# SW6106_A_A_B_C_MCU_LED.net
KiCad netlist of a schematic drawn in Altium Designer
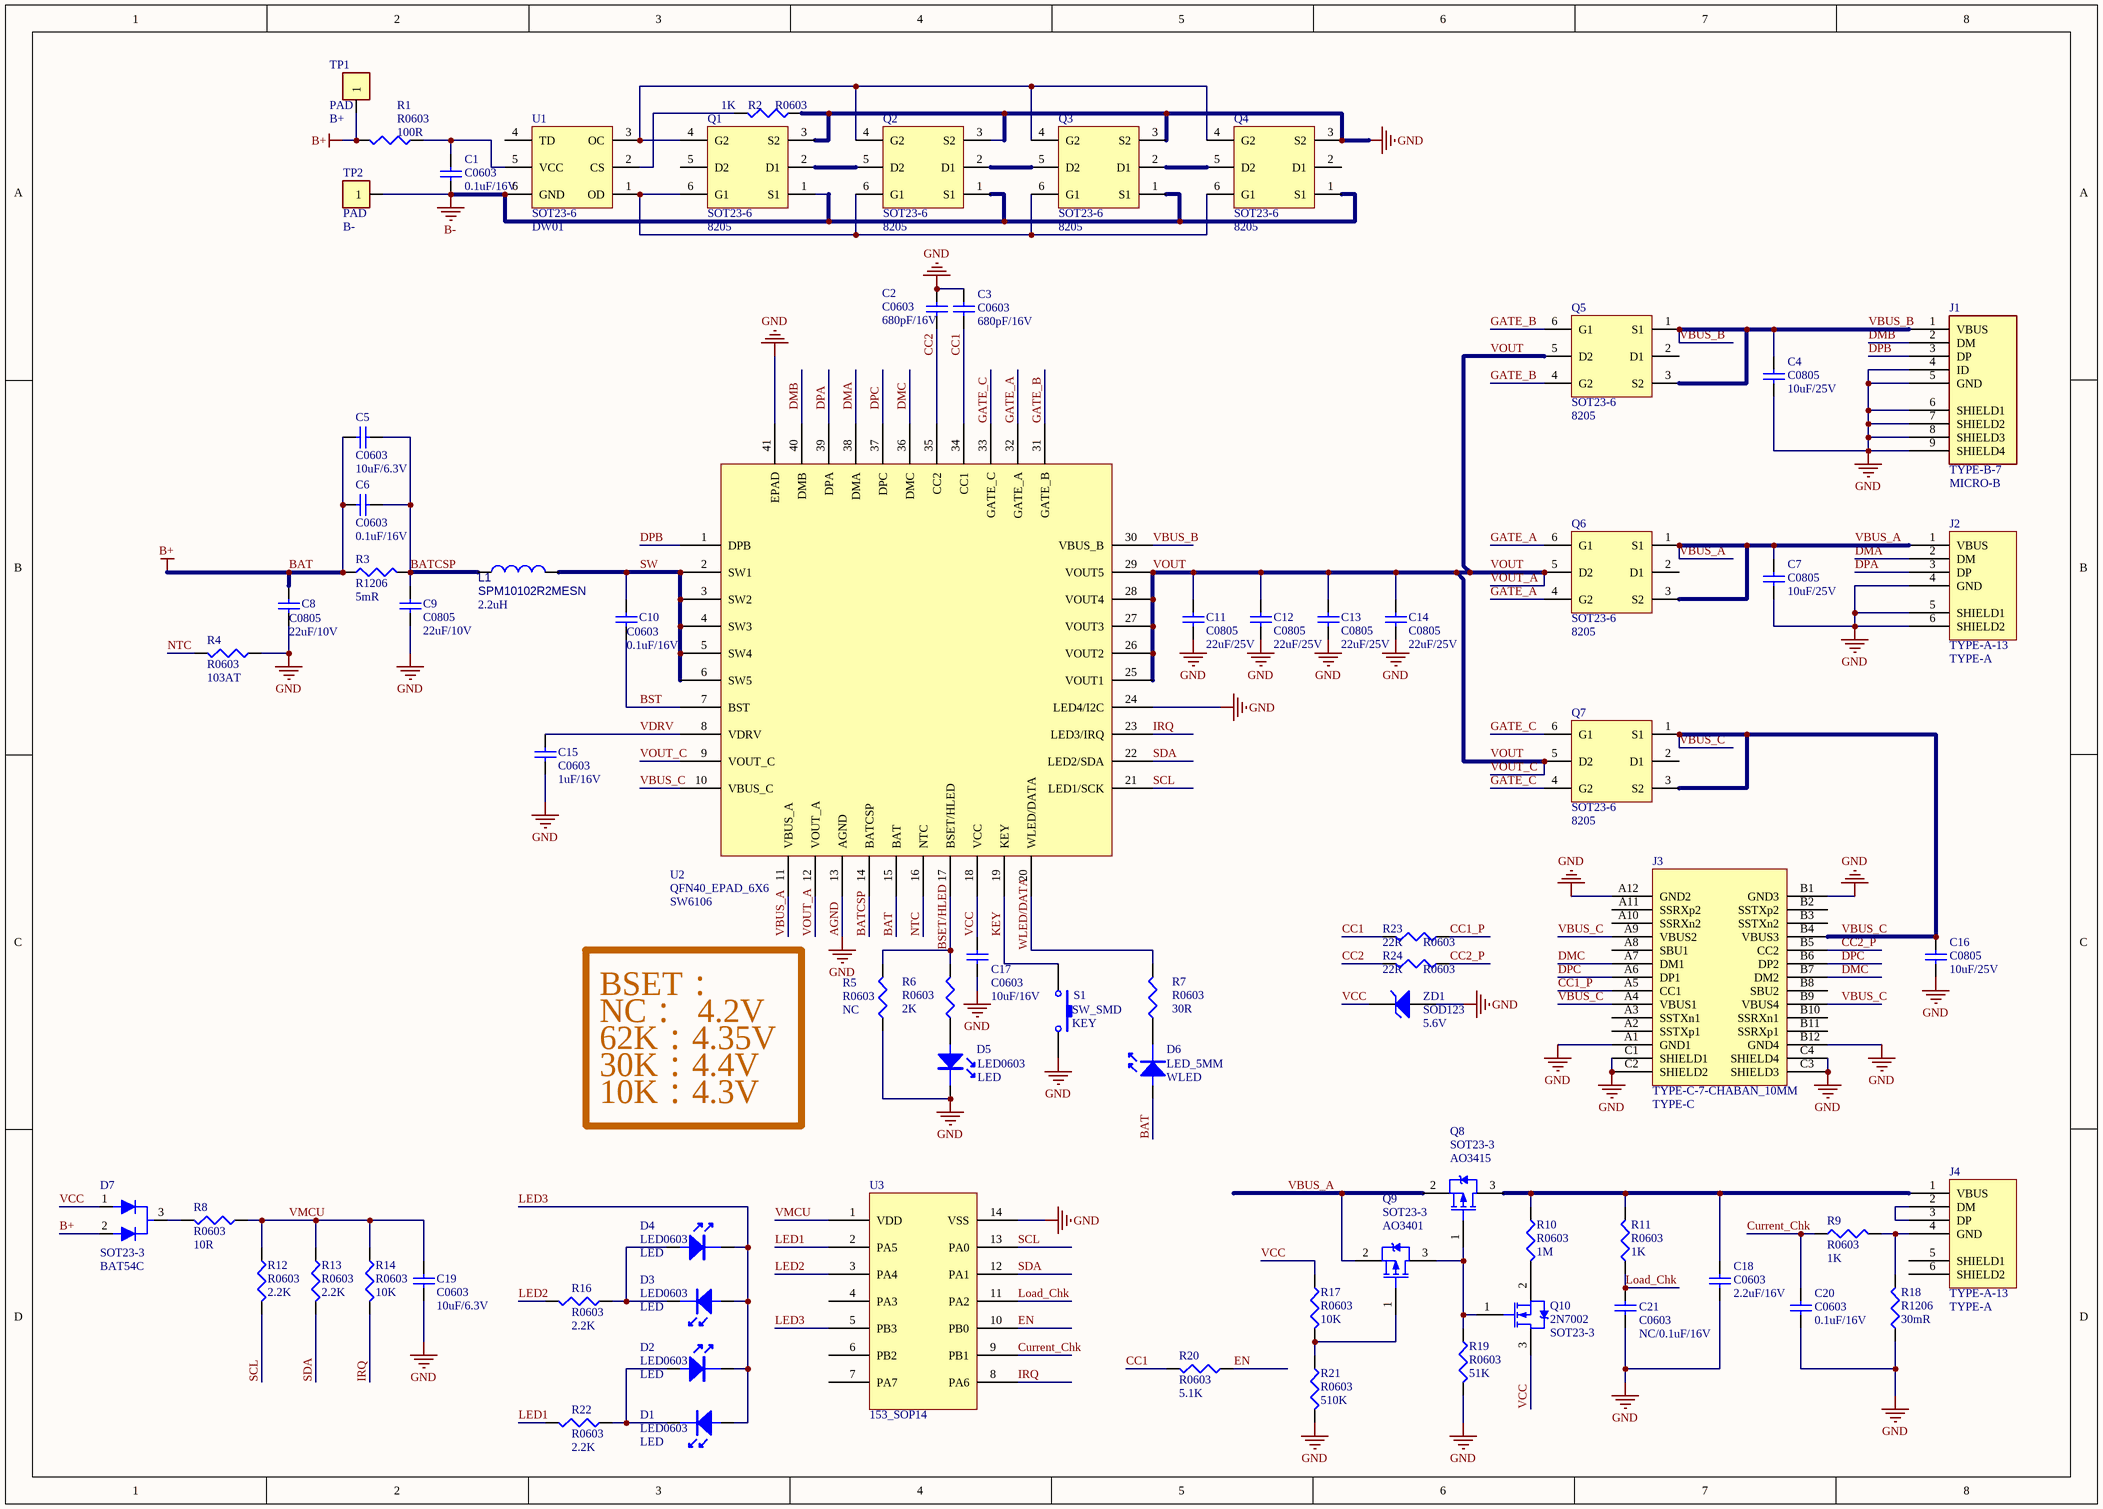
[diagram p0: SW6106+A+A+B+C+MCU+LED.SchDoc]

(export (version "E")
  (design (tool "Eeschema 10.0.6"))
  (components
    (comp (ref "C1")
      (value "C0603")
      (footprint "C0603")
      (description "Capacitor")
      (fields (field (name "ALTIUM_VALUE") "0.1uF/16V") (field (name "PUBLISHER") "Altium Limited"))
      (libsource (lib "*") (part "Cap"))
    )
    (comp (ref "C2")
      (value "C0603")
      (footprint "C0603")
      (description "Capacitor")
      (fields (field (name "ALTIUM_VALUE") "680pF/16V") (field (name "PUBLISHER") "Altium Limited"))
      (libsource (lib "*") (part "CAP0603"))
    )
    (comp (ref "C3")
      (value "C0603")
      (footprint "C0603")
      (description "Capacitor")
      (fields (field (name "ALTIUM_VALUE") "680pF/16V") (field (name "PUBLISHER") "Altium Limited"))
      (libsource (lib "*") (part "CAP0603"))
    )
    (comp (ref "C4")
      (value "C0805")
      (footprint "C0805")
      (description "Capacitor")
      (fields (field (name "ALTIUM_VALUE") "10uF/25V") (field (name "PUBLISHER") "Altium Limited"))
      (libsource (lib "*") (part "CAP0603"))
    )
    (comp (ref "C5")
      (value "C0603")
      (footprint "C0603")
      (description "Capacitor")
      (fields (field (name "ALTIUM_VALUE") "10uF/6.3V") (field (name "PUBLISHER") "Altium Limited"))
      (libsource (lib "*") (part "CAP0603"))
    )
    (comp (ref "C6")
      (value "C0603")
      (footprint "C0603")
      (description "Capacitor")
      (fields (field (name "ALTIUM_VALUE") "0.1uF/16V") (field (name "PUBLISHER") "Altium Limited"))
      (libsource (lib "*") (part "CAP0603"))
    )
    (comp (ref "C7")
      (value "C0805")
      (footprint "C0805")
      (description "Capacitor")
      (fields (field (name "ALTIUM_VALUE") "10uF/25V") (field (name "PUBLISHER") "Altium Limited"))
      (libsource (lib "*") (part "CAP0603"))
    )
    (comp (ref "C8")
      (value "C0805")
      (footprint "C0805")
      (description "Capacitor")
      (fields (field (name "ALTIUM_VALUE") "22uF/10V") (field (name "PUBLISHER") "Altium Limited"))
      (libsource (lib "*") (part "CAP0805"))
    )
    (comp (ref "C9")
      (value "C0805")
      (footprint "C0805")
      (description "Capacitor")
      (fields (field (name "ALTIUM_VALUE") "22uF/10V") (field (name "PUBLISHER") "Altium Limited"))
      (libsource (lib "*") (part "CAP0805"))
    )
    (comp (ref "C10")
      (value "C0603")
      (footprint "C0603")
      (description "Capacitor")
      (fields (field (name "ALTIUM_VALUE") "0.1uF/16V") (field (name "PUBLISHER") "Altium Limited"))
      (libsource (lib "*") (part "CAP0603"))
    )
    (comp (ref "C11")
      (value "C0805")
      (footprint "C0805")
      (description "Capacitor")
      (fields (field (name "ALTIUM_VALUE") "22uF/25V") (field (name "PUBLISHER") "Altium Limited"))
      (libsource (lib "*") (part "CAP0805"))
    )
    (comp (ref "C12")
      (value "C0805")
      (footprint "C0805")
      (description "Capacitor")
      (fields (field (name "ALTIUM_VALUE") "22uF/25V") (field (name "PUBLISHER") "Altium Limited"))
      (libsource (lib "*") (part "CAP0805"))
    )
    (comp (ref "C13")
      (value "C0805")
      (footprint "C0805")
      (description "Capacitor")
      (fields (field (name "ALTIUM_VALUE") "22uF/25V") (field (name "PUBLISHER") "Altium Limited"))
      (libsource (lib "*") (part "CAP0805"))
    )
    (comp (ref "C14")
      (value "C0805")
      (footprint "C0805")
      (description "Capacitor")
      (fields (field (name "ALTIUM_VALUE") "22uF/25V") (field (name "PUBLISHER") "Altium Limited"))
      (libsource (lib "*") (part "CAP0805"))
    )
    (comp (ref "C15")
      (value "C0603")
      (footprint "C0603")
      (description "Capacitor")
      (fields (field (name "ALTIUM_VALUE") "1uF/16V") (field (name "PUBLISHER") "Altium Limited"))
      (libsource (lib "*") (part "CAP0603"))
    )
    (comp (ref "C16")
      (value "C0805")
      (footprint "C0805")
      (description "Capacitor")
      (fields (field (name "ALTIUM_VALUE") "10uF/25V") (field (name "PUBLISHER") "Altium Limited"))
      (libsource (lib "*") (part "CAP0603"))
    )
    (comp (ref "C17")
      (value "C0603")
      (footprint "C0603")
      (description "Capacitor")
      (fields (field (name "ALTIUM_VALUE") "10uF/16V") (field (name "PUBLISHER") "Altium Limited"))
      (libsource (lib "*") (part "CAP0603"))
    )
    (comp (ref "C18")
      (value "C0603")
      (footprint "C0603")
      (description "Capacitor")
      (fields (field (name "ALTIUM_VALUE") "2.2uF/16V") (field (name "PUBLISHER") "Altium Limited"))
      (libsource (lib "*") (part "CAP0603"))
    )
    (comp (ref "C19")
      (value "C0603")
      (footprint "C0603")
      (description "Capacitor")
      (fields (field (name "ALTIUM_VALUE") "10uF/6.3V") (field (name "PUBLISHER") "Altium Limited"))
      (libsource (lib "*") (part "CAP0603"))
    )
    (comp (ref "C20")
      (value "C0603")
      (footprint "C0603")
      (description "Capacitor")
      (fields (field (name "ALTIUM_VALUE") "0.1uF/16V") (field (name "PUBLISHER") "Altium Limited"))
      (libsource (lib "*") (part "CAP0603"))
    )
    (comp (ref "C21")
      (value "C0603")
      (footprint "C0603")
      (description "Capacitor")
      (fields (field (name "ALTIUM_VALUE") "NC/0.1uF/16V") (field (name "PUBLISHER") "Altium Limited"))
      (libsource (lib "*") (part "CAP0603"))
    )
    (comp (ref "D1") (value "LED") (footprint "LED0603") (libsource (lib "*") (part "LED")))
    (comp (ref "D2") (value "LED") (footprint "LED0603") (libsource (lib "*") (part "LED")))
    (comp (ref "D3") (value "LED") (footprint "LED0603") (libsource (lib "*") (part "LED")))
    (comp (ref "D4") (value "LED") (footprint "LED0603") (libsource (lib "*") (part "LED")))
    (comp (ref "D5") (value "LED") (footprint "LED0603") (libsource (lib "*") (part "LED")))
    (comp (ref "D6")
      (value "WLED")
      (footprint "LED_5MM")
      (fields (field (name "FOOTPRINF") "LED_5MM") (field (name "Comment") "LED_5MM"))
      (libsource (lib "*") (part "LED"))
    )
    (comp (ref "D7") (value "BAT54C") (footprint "SOT23-3") (libsource (lib "Schlib1-2012") (part "D3")))
    (comp (ref "J1")
      (value "MICRO-B")
      (footprint "TYPE-B-7")
      (fields (field (name "FOOTPRINTF") "TYPE-B-7") (field (name "Comment") "USB_MICRO_B"))
      (libsource (lib "*") (part "USB_MICRO_B"))
    )
    (comp (ref "J2")
      (value "TYPE-A")
      (footprint "TYPE-A-13")
      (fields (field (name "FOOTPRINF") "TYPE-A-13") (field (name "Comment") "TYPE-A-1"))
      (libsource (lib "*") (part "TYPE-A-1"))
    )
    (comp (ref "J3")
      (value "TYPE-C")
      (footprint "TYPE-C-7-CHABAN_10MM")
      (libsource (lib "*") (part "TYPE-C"))
    )
    (comp (ref "J4")
      (value "TYPE-A")
      (footprint "PIE10-USB")
      (fields (field (name "FOOTPRINF") "TYPE-A-13") (field (name "Comment") "TYPE-A-1"))
      (libsource (lib "*") (part "TYPE-A-1"))
    )
    (comp (ref "L1")
      (value "SPM10102R2MESN")
      (footprint "INDUCTOR_SPM1010")
      (fields (field (name "ALTIUM_VALUE") "2.2uH"))
      (libsource (lib "*") (part "INDUCTOR"))
    )
    (comp (ref "Q1")
      (value "8205")
      (footprint "SOT23-6")
      (fields (field (name "FOOTPRINF") "SOT23-6"))
      (libsource (lib "*") (part "8205B"))
    )
    (comp (ref "Q2")
      (value "8205")
      (footprint "SOT23-6")
      (fields (field (name "FOOTPRINF") "SOT23-6"))
      (libsource (lib "*") (part "8205B"))
    )
    (comp (ref "Q3")
      (value "8205")
      (footprint "SOT23-6")
      (fields (field (name "FOOTPRINF") "SOT23-6"))
      (libsource (lib "*") (part "8205B"))
    )
    (comp (ref "Q4")
      (value "8205")
      (footprint "SOT23-6")
      (fields (field (name "FOOTPRINF") "SOT23-6"))
      (libsource (lib "*") (part "8205B"))
    )
    (comp (ref "Q5")
      (value "8205")
      (footprint "SOT23-6")
      (fields (field (name "FOOTPRINF") "SOT23-6"))
      (libsource (lib "") (part "8205B_1"))
    )
    (comp (ref "Q6")
      (value "8205")
      (footprint "SOT23-6")
      (fields (field (name "FOOTPRINF") "SOT23-6"))
      (libsource (lib "") (part "8205B_1"))
    )
    (comp (ref "Q7")
      (value "8205")
      (footprint "SOT23-6")
      (fields (field (name "FOOTPRINF") "SOT23-6"))
      (libsource (lib "") (part "8205B_1"))
    )
    (comp (ref "Q8")
      (value "AO3415")
      (footprint "SOT23-3")
      (description "P-Channel Power MOSFET")
      (fields (field (name "Comment") "PMOS-2") (field (name "PUBLISHER") "Altium Limited"))
      (libsource (lib "Miscellaneous Devices") (part "PMOS-2"))
    )
    (comp (ref "Q9")
      (value "AO3401")
      (footprint "SOT23-3")
      (description "P-Channel Power MOSFET")
      (fields (field (name "Comment") "PMOS-2") (field (name "PUBLISHER") "Altium Limited"))
      (libsource (lib "Miscellaneous Devices") (part "PMOS-2"))
    )
    (comp (ref "Q10")
      (value "2N7002")
      (footprint "SOT23-3")
      (description "N-Channel Power MOSFET")
      (fields (field (name "Comment") "NMOS-2") (field (name "PUBLISHER") "Altium Limited"))
      (libsource (lib "Miscellaneous Devices") (part "NMOS-2"))
    )
    (comp (ref "R1")
      (value "R0603")
      (footprint "R0603")
      (description "Resistor")
      (fields (field (name "ALTIUM_VALUE") "100R") (field (name "PUBLISHER") "Altium Limited"))
      (libsource (lib "*") (part "Res3"))
    )
    (comp (ref "R2")
      (value "R0603")
      (footprint "R0603")
      (description "Resistor")
      (fields (field (name "ALTIUM_VALUE") "1K") (field (name "PUBLISHER") "Altium Limited"))
      (libsource (lib "*") (part "Res3"))
    )
    (comp (ref "R3")
      (value "R1206")
      (footprint "R1206")
      (description "Resistor")
      (fields (field (name "ALTIUM_VALUE") "5mR") (field (name "PUBLISHER") "Altium Limited"))
      (libsource (lib "*") (part "RES"))
    )
    (comp (ref "R4")
      (value "R0603")
      (footprint "R0603")
      (description "Resistor")
      (fields (field (name "ALTIUM_VALUE") "103AT") (field (name "PUBLISHER") "Altium Limited"))
      (libsource (lib "*") (part "RES"))
    )
    (comp (ref "R5")
      (value "R0603")
      (footprint "R0603")
      (description "Resistor")
      (fields (field (name "ALTIUM_VALUE") "NC") (field (name "PUBLISHER") "Altium Limited"))
      (libsource (lib "*") (part "RES"))
    )
    (comp (ref "R6")
      (value "R0603")
      (footprint "R0603")
      (description "Resistor")
      (fields (field (name "ALTIUM_VALUE") "2K") (field (name "PUBLISHER") "Altium Limited"))
      (libsource (lib "*") (part "RES"))
    )
    (comp (ref "R7")
      (value "R0603")
      (footprint "R0603")
      (description "Resistor")
      (fields (field (name "ALTIUM_VALUE") "30R") (field (name "PUBLISHER") "Altium Limited"))
      (libsource (lib "*") (part "RES"))
    )
    (comp (ref "R8")
      (value "R0603")
      (footprint "R0603")
      (description "Resistor")
      (fields (field (name "ALTIUM_VALUE") "10R") (field (name "PUBLISHER") "Altium Limited"))
      (libsource (lib "*") (part "RES"))
    )
    (comp (ref "R9")
      (value "R0603")
      (footprint "R0603")
      (description "Resistor")
      (fields (field (name "ALTIUM_VALUE") "1K") (field (name "PUBLISHER") "Altium Limited"))
      (libsource (lib "*") (part "RES"))
    )
    (comp (ref "R10")
      (value "R0603")
      (footprint "R0603")
      (description "Resistor")
      (fields (field (name "ALTIUM_VALUE") "1M") (field (name "PUBLISHER") "Altium Limited"))
      (libsource (lib "*") (part "RES"))
    )
    (comp (ref "R11")
      (value "R0603")
      (footprint "R0603")
      (description "Resistor")
      (fields (field (name "ALTIUM_VALUE") "1K") (field (name "PUBLISHER") "Altium Limited"))
      (libsource (lib "*") (part "RES"))
    )
    (comp (ref "R12")
      (value "R0603")
      (footprint "R0603")
      (description "Resistor")
      (fields (field (name "ALTIUM_VALUE") "2.2K") (field (name "PUBLISHER") "Altium Limited"))
      (libsource (lib "*") (part "RES"))
    )
    (comp (ref "R13")
      (value "R0603")
      (footprint "R0603")
      (description "Resistor")
      (fields (field (name "ALTIUM_VALUE") "2.2K") (field (name "PUBLISHER") "Altium Limited"))
      (libsource (lib "*") (part "RES"))
    )
    (comp (ref "R14")
      (value "R0603")
      (footprint "R0603")
      (description "Resistor")
      (fields (field (name "ALTIUM_VALUE") "10K") (field (name "PUBLISHER") "Altium Limited"))
      (libsource (lib "*") (part "RES"))
    )
    (comp (ref "R16")
      (value "R0603")
      (footprint "R0603")
      (description "Resistor")
      (fields (field (name "ALTIUM_VALUE") "2.2K") (field (name "PUBLISHER") "Altium Limited"))
      (libsource (lib "*") (part "RES"))
    )
    (comp (ref "R17")
      (value "R0603")
      (footprint "R0603")
      (description "Resistor")
      (fields (field (name "ALTIUM_VALUE") "10K") (field (name "PUBLISHER") "Altium Limited"))
      (libsource (lib "*") (part "RES"))
    )
    (comp (ref "R18")
      (value "R1206")
      (footprint "C-1206A")
      (description "Resistor")
      (fields (field (name "ALTIUM_VALUE") "30mR") (field (name "PUBLISHER") "Altium Limited"))
      (libsource (lib "*") (part "RES"))
    )
    (comp (ref "R19")
      (value "R0603")
      (footprint "R0603")
      (description "Resistor")
      (fields (field (name "ALTIUM_VALUE") "51K") (field (name "PUBLISHER") "Altium Limited"))
      (libsource (lib "*") (part "RES"))
    )
    (comp (ref "R20")
      (value "R0603")
      (footprint "R0603")
      (description "Resistor")
      (fields (field (name "ALTIUM_VALUE") "5.1K") (field (name "PUBLISHER") "Altium Limited"))
      (libsource (lib "*") (part "RES"))
    )
    (comp (ref "R21")
      (value "R0603")
      (footprint "R0603")
      (description "Resistor")
      (fields (field (name "ALTIUM_VALUE") "510K") (field (name "PUBLISHER") "Altium Limited"))
      (libsource (lib "*") (part "RES"))
    )
    (comp (ref "R22")
      (value "R0603")
      (footprint "R0603")
      (description "Resistor")
      (fields (field (name "ALTIUM_VALUE") "2.2K") (field (name "PUBLISHER") "Altium Limited"))
      (libsource (lib "*") (part "RES"))
    )
    (comp (ref "R23")
      (value "R0603")
      (footprint "R0603")
      (description "Resistor")
      (fields (field (name "ALTIUM_VALUE") "22R") (field (name "PUBLISHER") "Altium Limited"))
      (libsource (lib "*") (part "RES"))
    )
    (comp (ref "R24")
      (value "R0603")
      (footprint "R0603")
      (description "Resistor")
      (fields (field (name "ALTIUM_VALUE") "22R") (field (name "PUBLISHER") "Altium Limited"))
      (libsource (lib "*") (part "RES"))
    )
    (comp (ref "S1")
      (value "KEY")
      (footprint "SW_SMD")
      (fields (field (name "FOOTPRINF") "SW_SMD"))
      (libsource (lib "*") (part "SW K"))
    )
    (comp (ref "TP1") (value "B+") (footprint "PAD") (libsource (lib "*") (part "Test Point")))
    (comp (ref "TP2") (value "B-") (footprint "PAD") (libsource (lib "") (part "Test Point_1")))
    (comp (ref "U1")
      (value "DW01")
      (footprint "SOT23-6")
      (fields (field (name "FOOTPRINF") "SOT23-6"))
      (libsource (lib "*") (part "DW01"))
    )
    (comp (ref "U2")
      (value "SW6106")
      (footprint "QFN40_EPAD_6X6")
      (libsource (lib "TEST") (part "SW6106_AFC"))
    )
    (comp (ref "U3") (value "153_SOP14") (libsource (lib "TEST") (part "153_SOP14")))
    (comp (ref "ZD1")
      (value "SOD123")
      (footprint "SOD-123")
      (description "Zener Diode")
      (fields (field (name "ALTIUM_UNNAMED_1") "5.6V"))
      (libsource (lib "Miscellaneous Devices") (part "D Zener"))
    )
  )
  (nets
    (net (code "1") (name "/BATCSP") (class "Default")
      (node (ref "C5") (pin "2") (pinfunction "2_2") (pintype "passive"))
      (node (ref "C6") (pin "2") (pinfunction "2_2") (pintype "passive"))
      (node (ref "C9") (pin "2") (pinfunction "2_2") (pintype "passive"))
      (node (ref "L1") (pin "1") (pinfunction "1_1") (pintype "passive"))
      (node (ref "R3") (pin "2") (pinfunction "2_2") (pintype "passive"))
      (node (ref "U2") (pin "14") (pinfunction "BATCSP_14") (pintype "passive"))
    )
    (net (code "2") (name "/BSET{slash}HLED") (class "Default")
      (node (ref "R5") (pin "2") (pinfunction "2_2") (pintype "passive"))
      (node (ref "R6") (pin "2") (pinfunction "2_2") (pintype "passive"))
      (node (ref "U2") (pin "17") (pinfunction "BSET/HLED_17") (pintype "passive"))
    )
    (net (code "3") (name "/BST") (class "Default")
      (node (ref "C10") (pin "1") (pinfunction "1_1") (pintype "passive"))
      (node (ref "U2") (pin "7") (pinfunction "BST_7") (pintype "passive"))
    )
    (net (code "4") (name "/CC1") (class "Default")
      (node (ref "C3") (pin "1") (pinfunction "1_1") (pintype "passive"))
      (node (ref "R20") (pin "2") (pinfunction "2_2") (pintype "passive"))
      (node (ref "R23") (pin "2") (pinfunction "2_2") (pintype "passive"))
      (node (ref "U2") (pin "34") (pinfunction "CC1_34") (pintype "passive"))
    )
    (net (code "5") (name "/CC1_P") (class "Default")
      (node (ref "J3") (pin "A5") (pinfunction "CC1_A5") (pintype "passive"))
      (node (ref "R23") (pin "1") (pinfunction "1_1") (pintype "passive"))
    )
    (net (code "6") (name "/CC2") (class "Default")
      (node (ref "C2") (pin "1") (pinfunction "1_1") (pintype "passive"))
      (node (ref "R24") (pin "2") (pinfunction "2_2") (pintype "passive"))
      (node (ref "U2") (pin "35") (pinfunction "CC2_35") (pintype "passive"))
    )
    (net (code "7") (name "/CC2_P") (class "Default")
      (node (ref "J3") (pin "B5") (pinfunction "CC2_B5") (pintype "passive"))
      (node (ref "R24") (pin "1") (pinfunction "1_1") (pintype "passive"))
    )
    (net (code "8") (name "/Current_Chk") (class "Default")
      (node (ref "C20") (pin "2") (pinfunction "2_2") (pintype "passive"))
      (node (ref "R9") (pin "1") (pinfunction "1_1") (pintype "passive"))
      (node (ref "U3") (pin "9") (pinfunction "PB1_9") (pintype "passive"))
    )
    (net (code "9") (name "/DMA") (class "Default")
      (node (ref "J2") (pin "2") (pinfunction "DM_2") (pintype "passive"))
      (node (ref "U2") (pin "38") (pinfunction "DMA_38") (pintype "passive"))
    )
    (net (code "10") (name "/DMB") (class "Default")
      (node (ref "J1") (pin "2") (pinfunction "DM_2") (pintype "passive"))
      (node (ref "U2") (pin "40") (pinfunction "DMB_40") (pintype "passive"))
    )
    (net (code "11") (name "/DMC") (class "Default")
      (node (ref "J3") (pin "A7") (pinfunction "DM1_A7") (pintype "passive"))
      (node (ref "J3") (pin "B7") (pinfunction "DM2_B7") (pintype "passive"))
      (node (ref "U2") (pin "36") (pinfunction "DMC_36") (pintype "passive"))
    )
    (net (code "12") (name "/DPA") (class "Default")
      (node (ref "J2") (pin "3") (pinfunction "DP_3") (pintype "passive"))
      (node (ref "U2") (pin "39") (pinfunction "DPA_39") (pintype "passive"))
    )
    (net (code "13") (name "/DPB") (class "Default")
      (node (ref "J1") (pin "3") (pinfunction "DP_3") (pintype "passive"))
      (node (ref "U2") (pin "1") (pinfunction "DPB_1") (pintype "passive"))
    )
    (net (code "14") (name "/DPC") (class "Default")
      (node (ref "J3") (pin "A6") (pinfunction "DP1_A6") (pintype "passive"))
      (node (ref "J3") (pin "B6") (pinfunction "DP2_B6") (pintype "passive"))
      (node (ref "U2") (pin "37") (pinfunction "DPC_37") (pintype "passive"))
    )
    (net (code "15") (name "/EN") (class "Default")
      (node (ref "R20") (pin "1") (pinfunction "1_1") (pintype "passive"))
      (node (ref "U3") (pin "10") (pinfunction "PB0_10") (pintype "passive"))
    )
    (net (code "16") (name "/GATE_A") (class "Default")
      (node (ref "Q6") (pin "4") (pinfunction "G2_4") (pintype "passive"))
      (node (ref "Q6") (pin "6") (pinfunction "G1_6") (pintype "passive"))
      (node (ref "U2") (pin "32") (pinfunction "GATE_A_32") (pintype "passive"))
    )
    (net (code "17") (name "/GATE_B") (class "Default")
      (node (ref "Q5") (pin "4") (pinfunction "G2_4") (pintype "passive"))
      (node (ref "Q5") (pin "6") (pinfunction "G1_6") (pintype "passive"))
      (node (ref "U2") (pin "31") (pinfunction "GATE_B_31") (pintype "passive"))
    )
    (net (code "18") (name "/GATE_C") (class "Default")
      (node (ref "Q7") (pin "4") (pinfunction "G2_4") (pintype "passive"))
      (node (ref "Q7") (pin "6") (pinfunction "G1_6") (pintype "passive"))
      (node (ref "U2") (pin "33") (pinfunction "GATE_C_33") (pintype "passive"))
    )
    (net (code "19") (name "/IRQ") (class "Default")
      (node (ref "R14") (pin "2") (pinfunction "2_2") (pintype "passive"))
      (node (ref "U2") (pin "23") (pinfunction "LED3/IRQ_23") (pintype "passive"))
      (node (ref "U3") (pin "8") (pinfunction "PA6_8") (pintype "passive"))
    )
    (net (code "20") (name "/KEY") (class "Default")
      (node (ref "S1") (pin "1") (pinfunction "1_1") (pintype "passive"))
      (node (ref "U2") (pin "19") (pinfunction "KEY_19") (pintype "passive"))
    )
    (net (code "21") (name "/LED1") (class "Default")
      (node (ref "R22") (pin "2") (pinfunction "2_2") (pintype "passive"))
      (node (ref "U3") (pin "2") (pinfunction "PA5_2") (pintype "passive"))
    )
    (net (code "22") (name "/LED2") (class "Default")
      (node (ref "R16") (pin "2") (pinfunction "2_2") (pintype "passive"))
      (node (ref "U3") (pin "3") (pinfunction "PA4_3") (pintype "passive"))
    )
    (net (code "23") (name "/LED3") (class "Default")
      (node (ref "D1") (pin "1") (pinfunction "A_1") (pintype "passive"))
      (node (ref "D2") (pin "2") (pinfunction "K_2") (pintype "passive"))
      (node (ref "D3") (pin "1") (pinfunction "A_1") (pintype "passive"))
      (node (ref "D4") (pin "2") (pinfunction "K_2") (pintype "passive"))
      (node (ref "U3") (pin "5") (pinfunction "PB3_5") (pintype "passive"))
    )
    (net (code "24") (name "/Load_Chk") (class "Default")
      (node (ref "C21") (pin "2") (pinfunction "2_2") (pintype "passive"))
      (node (ref "R11") (pin "1") (pinfunction "1_1") (pintype "passive"))
      (node (ref "U3") (pin "11") (pinfunction "PA2_11") (pintype "passive"))
    )
    (net (code "25") (name "/NTC") (class "Default")
      (node (ref "R4") (pin "2") (pinfunction "2_2") (pintype "passive"))
      (node (ref "U2") (pin "16") (pinfunction "NTC_16") (pintype "passive"))
    )
    (net (code "26") (name "/SCL") (class "Default")
      (node (ref "R12") (pin "2") (pinfunction "2_2") (pintype "passive"))
      (node (ref "U2") (pin "21") (pinfunction "LED1/SCK_21") (pintype "passive"))
      (node (ref "U3") (pin "13") (pinfunction "PA0_13") (pintype "passive"))
    )
    (net (code "27") (name "/SDA") (class "Default")
      (node (ref "R13") (pin "2") (pinfunction "2_2") (pintype "passive"))
      (node (ref "U2") (pin "22") (pinfunction "LED2/SDA_22") (pintype "passive"))
      (node (ref "U3") (pin "12") (pinfunction "PA1_12") (pintype "passive"))
    )
    (net (code "28") (name "/SW") (class "Default")
      (node (ref "C10") (pin "2") (pinfunction "2_2") (pintype "passive"))
      (node (ref "L1") (pin "2") (pinfunction "2_2") (pintype "passive"))
      (node (ref "U2") (pin "2") (pinfunction "SW1_2") (pintype "passive"))
      (node (ref "U2") (pin "3") (pinfunction "SW2_3") (pintype "passive"))
      (node (ref "U2") (pin "4") (pinfunction "SW3_4") (pintype "passive"))
      (node (ref "U2") (pin "5") (pinfunction "SW4_5") (pintype "passive"))
      (node (ref "U2") (pin "6") (pinfunction "SW5_6") (pintype "passive"))
    )
    (net (code "29") (name "/VBUS_A") (class "Default")
      (node (ref "C7") (pin "2") (pinfunction "2_2") (pintype "passive"))
      (node (ref "J2") (pin "1") (pinfunction "VBUS_1") (pintype "passive"))
      (node (ref "Q6") (pin "1") (pinfunction "S1_1") (pintype "passive"))
      (node (ref "Q6") (pin "3") (pinfunction "S2_3") (pintype "passive"))
      (node (ref "Q8") (pin "2") (pinfunction "S_2") (pintype "passive"))
      (node (ref "Q9") (pin "2") (pinfunction "S_2") (pintype "passive"))
      (node (ref "U2") (pin "11") (pinfunction "VBUS_A_11") (pintype "passive"))
    )
    (net (code "30") (name "/VBUS_B") (class "Default")
      (node (ref "C4") (pin "2") (pinfunction "2_2") (pintype "passive"))
      (node (ref "J1") (pin "1") (pinfunction "VBUS_1") (pintype "passive"))
      (node (ref "Q5") (pin "1") (pinfunction "S1_1") (pintype "passive"))
      (node (ref "Q5") (pin "3") (pinfunction "S2_3") (pintype "passive"))
      (node (ref "U2") (pin "30") (pinfunction "VBUS_B_30") (pintype "passive"))
    )
    (net (code "31") (name "/VBUS_C") (class "Default")
      (node (ref "C16") (pin "2") (pinfunction "2_2") (pintype "passive"))
      (node (ref "J3") (pin "A4") (pinfunction "VBUS1_A4") (pintype "passive"))
      (node (ref "J3") (pin "A9") (pinfunction "VBUS2_A9") (pintype "passive"))
      (node (ref "J3") (pin "B4") (pinfunction "VBUS3_B4") (pintype "passive"))
      (node (ref "J3") (pin "B9") (pinfunction "VBUS4_B9") (pintype "passive"))
      (node (ref "Q7") (pin "1") (pinfunction "S1_1") (pintype "passive"))
      (node (ref "Q7") (pin "3") (pinfunction "S2_3") (pintype "passive"))
      (node (ref "U2") (pin "10") (pinfunction "VBUS_C_10") (pintype "passive"))
    )
    (net (code "32") (name "/VCC") (class "Default")
      (node (ref "C17") (pin "2") (pinfunction "2_2") (pintype "passive"))
      (node (ref "D7") (pin "1") (pintype "passive"))
      (node (ref "Q10") (pin "3") (pinfunction "D_3") (pintype "passive"))
      (node (ref "R17") (pin "1") (pinfunction "1_1") (pintype "passive"))
      (node (ref "U2") (pin "18") (pinfunction "VCC_18") (pintype "passive"))
      (node (ref "ZD1") (pin "2") (pinfunction "K_2") (pintype "passive"))
    )
    (net (code "33") (name "/VDRV") (class "Default")
      (node (ref "C15") (pin "2") (pinfunction "2_2") (pintype "passive"))
      (node (ref "U2") (pin "8") (pinfunction "VDRV_8") (pintype "passive"))
    )
    (net (code "34") (name "/VMCU") (class "Default")
      (node (ref "C19") (pin "1") (pinfunction "1_1") (pintype "passive"))
      (node (ref "R12") (pin "1") (pinfunction "1_1") (pintype "passive"))
      (node (ref "R13") (pin "1") (pinfunction "1_1") (pintype "passive"))
      (node (ref "R14") (pin "1") (pinfunction "1_1") (pintype "passive"))
      (node (ref "R8") (pin "1") (pinfunction "1_1") (pintype "passive"))
      (node (ref "U3") (pin "1") (pinfunction "VDD_1") (pintype "passive"))
    )
    (net (code "35") (name "/VOUT") (class "Default")
      (node (ref "C11") (pin "2") (pinfunction "2_2") (pintype "passive"))
      (node (ref "C12") (pin "2") (pinfunction "2_2") (pintype "passive"))
      (node (ref "C13") (pin "2") (pinfunction "2_2") (pintype "passive"))
      (node (ref "C14") (pin "2") (pinfunction "2_2") (pintype "passive"))
      (node (ref "Q5") (pin "5") (pinfunction "D2_5") (pintype "passive"))
      (node (ref "Q6") (pin "5") (pinfunction "D2_5") (pintype "passive"))
      (node (ref "Q7") (pin "5") (pinfunction "D2_5") (pintype "passive"))
      (node (ref "U2") (pin "12") (pinfunction "VOUT_A_12") (pintype "passive"))
      (node (ref "U2") (pin "25") (pinfunction "VOUT1_25") (pintype "passive"))
      (node (ref "U2") (pin "26") (pinfunction "VOUT2_26") (pintype "passive"))
      (node (ref "U2") (pin "27") (pinfunction "VOUT3_27") (pintype "passive"))
      (node (ref "U2") (pin "28") (pinfunction "VOUT4_28") (pintype "passive"))
      (node (ref "U2") (pin "29") (pinfunction "VOUT5_29") (pintype "passive"))
      (node (ref "U2") (pin "9") (pinfunction "VOUT_C_9") (pintype "passive"))
    )
    (net (code "36") (name "/WLED{slash}DATA") (class "Default")
      (node (ref "R7") (pin "2") (pinfunction "2_2") (pintype "passive"))
      (node (ref "U2") (pin "20") (pinfunction "WLED/DATA_20") (pintype "passive"))
    )
    (net (code "37") (name "B+") (class "Default")
      (node (ref "C5") (pin "1") (pinfunction "1_1") (pintype "passive"))
      (node (ref "C6") (pin "1") (pinfunction "1_1") (pintype "passive"))
      (node (ref "C8") (pin "2") (pinfunction "2_2") (pintype "passive"))
      (node (ref "D6") (pin "1") (pinfunction "A_1") (pintype "passive"))
      (node (ref "D7") (pin "2") (pintype "passive"))
      (node (ref "R1") (pin "2") (pinfunction "2_2") (pintype "passive"))
      (node (ref "R3") (pin "1") (pinfunction "1_1") (pintype "passive"))
      (node (ref "TP1") (pin "1") (pinfunction "1_1") (pintype "passive"))
      (node (ref "U2") (pin "15") (pinfunction "BAT_15") (pintype "passive"))
    )
    (net (code "38") (name "B-") (class "Default")
      (node (ref "C1") (pin "1") (pinfunction "1_1") (pintype "passive"))
      (node (ref "Q1") (pin "1") (pinfunction "S1_1") (pintype "passive"))
      (node (ref "Q2") (pin "1") (pinfunction "S1_1") (pintype "passive"))
      (node (ref "Q3") (pin "1") (pinfunction "S1_1") (pintype "passive"))
      (node (ref "Q4") (pin "1") (pinfunction "S1_1") (pintype "passive"))
      (node (ref "TP2") (pin "1") (pinfunction "1_1") (pintype "passive"))
      (node (ref "U1") (pin "6") (pinfunction "GND_6") (pintype "passive"))
    )
    (net (code "39") (name "GND") (class "Default")
      (node (ref "C11") (pin "1") (pinfunction "1_1") (pintype "passive"))
      (node (ref "C12") (pin "1") (pinfunction "1_1") (pintype "passive"))
      (node (ref "C13") (pin "1") (pinfunction "1_1") (pintype "passive"))
      (node (ref "C14") (pin "1") (pinfunction "1_1") (pintype "passive"))
      (node (ref "C15") (pin "1") (pinfunction "1_1") (pintype "passive"))
      (node (ref "C16") (pin "1") (pinfunction "1_1") (pintype "passive"))
      (node (ref "C17") (pin "1") (pinfunction "1_1") (pintype "passive"))
      (node (ref "C18") (pin "1") (pinfunction "1_1") (pintype "passive"))
      (node (ref "C19") (pin "2") (pinfunction "2_2") (pintype "passive"))
      (node (ref "C2") (pin "2") (pinfunction "2_2") (pintype "passive"))
      (node (ref "C20") (pin "1") (pinfunction "1_1") (pintype "passive"))
      (node (ref "C21") (pin "1") (pinfunction "1_1") (pintype "passive"))
      (node (ref "C3") (pin "2") (pinfunction "2_2") (pintype "passive"))
      (node (ref "C4") (pin "1") (pinfunction "1_1") (pintype "passive"))
      (node (ref "C7") (pin "1") (pinfunction "1_1") (pintype "passive"))
      (node (ref "C8") (pin "1") (pinfunction "1_1") (pintype "passive"))
      (node (ref "C9") (pin "1") (pinfunction "1_1") (pintype "passive"))
      (node (ref "D5") (pin "2") (pinfunction "K_2") (pintype "passive"))
      (node (ref "J1") (pin "4") (pinfunction "ID_4") (pintype "passive"))
      (node (ref "J1") (pin "5") (pinfunction "GND_5") (pintype "passive"))
      (node (ref "J1") (pin "6") (pinfunction "SHIELD1_6") (pintype "passive"))
      (node (ref "J1") (pin "7") (pinfunction "SHIELD2_7") (pintype "passive"))
      (node (ref "J1") (pin "8") (pinfunction "SHIELD3_8") (pintype "passive"))
      (node (ref "J1") (pin "9") (pinfunction "SHIELD4_9") (pintype "passive"))
      (node (ref "J2") (pin "4") (pinfunction "GND_4") (pintype "passive"))
      (node (ref "J2") (pin "5") (pinfunction "SHIELD1_5") (pintype "passive"))
      (node (ref "J2") (pin "6") (pinfunction "SHIELD2_6") (pintype "passive"))
      (node (ref "J3") (pin "A1") (pinfunction "GND1_A1") (pintype "passive"))
      (node (ref "J3") (pin "A12") (pinfunction "GND2_A12") (pintype "passive"))
      (node (ref "J3") (pin "B1") (pinfunction "GND3_B1") (pintype "passive"))
      (node (ref "J3") (pin "B12") (pinfunction "GND4_B12") (pintype "passive"))
      (node (ref "J3") (pin "C1") (pinfunction "SHIELD1_C1") (pintype "passive"))
      (node (ref "J3") (pin "C2") (pinfunction "SHIELD2_C2") (pintype "passive"))
      (node (ref "J3") (pin "C3") (pinfunction "SHIELD3_C3") (pintype "passive"))
      (node (ref "J3") (pin "C4") (pinfunction "SHIELD4_C4") (pintype "passive"))
      (node (ref "Q1") (pin "3") (pinfunction "S2_3") (pintype "passive"))
      (node (ref "Q2") (pin "3") (pinfunction "S2_3") (pintype "passive"))
      (node (ref "Q3") (pin "3") (pinfunction "S2_3") (pintype "passive"))
      (node (ref "Q4") (pin "3") (pinfunction "S2_3") (pintype "passive"))
      (node (ref "R18") (pin "1") (pinfunction "1_1") (pintype "passive"))
      (node (ref "R19") (pin "2") (pinfunction "2_2") (pintype "passive"))
      (node (ref "R2") (pin "1") (pinfunction "1_1") (pintype "passive"))
      (node (ref "R21") (pin "2") (pinfunction "2_2") (pintype "passive"))
      (node (ref "R4") (pin "1") (pinfunction "1_1") (pintype "passive"))
      (node (ref "R5") (pin "1") (pinfunction "1_1") (pintype "passive"))
      (node (ref "S1") (pin "2") (pinfunction "2_2") (pintype "passive"))
      (node (ref "U2") (pin "13") (pinfunction "AGND_13") (pintype "passive"))
      (node (ref "U2") (pin "24") (pinfunction "LED4/I2C_24") (pintype "passive"))
      (node (ref "U2") (pin "41") (pinfunction "EPAD_41") (pintype "passive"))
      (node (ref "U3") (pin "14") (pinfunction "VSS_14") (pintype "passive"))
      (node (ref "ZD1") (pin "1") (pinfunction "A_1") (pintype "passive"))
    )
    (net (code "40") (name "Net-(D1-K)") (class "Default")
      (node (ref "D1") (pin "2") (pinfunction "K_2") (pintype "passive"))
      (node (ref "D2") (pin "1") (pinfunction "A_1") (pintype "passive"))
      (node (ref "R22") (pin "1") (pinfunction "1_1") (pintype "passive"))
    )
    (net (code "41") (name "Net-(D3-K)") (class "Default")
      (node (ref "D3") (pin "2") (pinfunction "K_2") (pintype "passive"))
      (node (ref "D4") (pin "1") (pinfunction "A_1") (pintype "passive"))
      (node (ref "R16") (pin "1") (pinfunction "1_1") (pintype "passive"))
    )
    (net (code "42") (name "Net-(D5-A)") (class "Default")
      (node (ref "D5") (pin "1") (pinfunction "A_1") (pintype "passive"))
      (node (ref "R6") (pin "1") (pinfunction "1_1") (pintype "passive"))
    )
    (net (code "43") (name "Net-(D6-K)") (class "Default")
      (node (ref "D6") (pin "2") (pinfunction "K_2") (pintype "passive"))
      (node (ref "R7") (pin "1") (pinfunction "1_1") (pintype "passive"))
    )
    (net (code "44") (name "Net-(D7-Pad3)") (class "Default")
      (node (ref "D7") (pin "3") (pintype "passive"))
      (node (ref "R8") (pin "2") (pinfunction "2_2") (pintype "passive"))
    )
    (net (code "45") (name "Net-(J4-DM)") (class "Default")
      (node (ref "J4") (pin "2") (pinfunction "DM_2") (pintype "passive"))
      (node (ref "J4") (pin "3") (pinfunction "DP_3") (pintype "passive"))
    )
    (net (code "46") (name "Net-(J4-GND)") (class "Default")
      (node (ref "J4") (pin "4") (pinfunction "GND_4") (pintype "passive"))
      (node (ref "R18") (pin "2") (pinfunction "2_2") (pintype "passive"))
      (node (ref "R9") (pin "2") (pinfunction "2_2") (pintype "passive"))
    )
    (net (code "47") (name "Net-(J4-VBUS)") (class "Default")
      (node (ref "C18") (pin "2") (pinfunction "2_2") (pintype "passive"))
      (node (ref "J4") (pin "1") (pinfunction "VBUS_1") (pintype "passive"))
      (node (ref "Q8") (pin "3") (pinfunction "D_3") (pintype "passive"))
      (node (ref "R10") (pin "1") (pinfunction "1_1") (pintype "passive"))
      (node (ref "R11") (pin "2") (pinfunction "2_2") (pintype "passive"))
    )
    (net (code "48") (name "Net-(Q1-D1)") (class "Default")
      (node (ref "Q1") (pin "2") (pinfunction "D1_2") (pintype "passive"))
      (node (ref "Q2") (pin "5") (pinfunction "D2_5") (pintype "passive"))
    )
    (net (code "49") (name "Net-(Q1-G1)") (class "Default")
      (node (ref "Q1") (pin "6") (pinfunction "G1_6") (pintype "passive"))
      (node (ref "Q2") (pin "6") (pinfunction "G1_6") (pintype "passive"))
      (node (ref "Q3") (pin "6") (pinfunction "G1_6") (pintype "passive"))
      (node (ref "Q4") (pin "6") (pinfunction "G1_6") (pintype "passive"))
      (node (ref "U1") (pin "1") (pinfunction "OD_1") (pintype "passive"))
    )
    (net (code "50") (name "Net-(Q1-G2)") (class "Default")
      (node (ref "Q1") (pin "4") (pinfunction "G2_4") (pintype "passive"))
      (node (ref "Q2") (pin "4") (pinfunction "G2_4") (pintype "passive"))
      (node (ref "Q3") (pin "4") (pinfunction "G2_4") (pintype "passive"))
      (node (ref "Q4") (pin "4") (pinfunction "G2_4") (pintype "passive"))
      (node (ref "U1") (pin "3") (pinfunction "OC_3") (pintype "passive"))
    )
    (net (code "51") (name "Net-(Q2-D1)") (class "Default")
      (node (ref "Q2") (pin "2") (pinfunction "D1_2") (pintype "passive"))
      (node (ref "Q3") (pin "5") (pinfunction "D2_5") (pintype "passive"))
    )
    (net (code "52") (name "Net-(Q3-D1)") (class "Default")
      (node (ref "Q3") (pin "2") (pinfunction "D1_2") (pintype "passive"))
      (node (ref "Q4") (pin "5") (pinfunction "D2_5") (pintype "passive"))
    )
    (net (code "53") (name "Net-(Q9-G)") (class "Default")
      (node (ref "Q9") (pin "1") (pinfunction "G_1") (pintype "passive"))
      (node (ref "R17") (pin "2") (pinfunction "2_2") (pintype "passive"))
      (node (ref "R21") (pin "1") (pinfunction "1_1") (pintype "passive"))
    )
    (net (code "54") (name "Net-(Q10-G)") (class "Default")
      (node (ref "Q10") (pin "1") (pinfunction "G_1") (pintype "passive"))
      (node (ref "Q8") (pin "1") (pinfunction "G_1") (pintype "passive"))
      (node (ref "Q9") (pin "3") (pinfunction "D_3") (pintype "passive"))
      (node (ref "R19") (pin "1") (pinfunction "1_1") (pintype "passive"))
    )
    (net (code "55") (name "Net-(Q10-S)") (class "Default")
      (node (ref "Q10") (pin "2") (pinfunction "S_2") (pintype "passive"))
      (node (ref "R10") (pin "2") (pinfunction "2_2") (pintype "passive"))
    )
    (net (code "56") (name "Net-(U1-CS)") (class "Default")
      (node (ref "R2") (pin "2") (pinfunction "2_2") (pintype "passive"))
      (node (ref "U1") (pin "2") (pinfunction "CS_2") (pintype "passive"))
    )
    (net (code "57") (name "Net-(U1-VCC)") (class "Default")
      (node (ref "C1") (pin "2") (pinfunction "2_2") (pintype "passive"))
      (node (ref "R1") (pin "1") (pinfunction "1_1") (pintype "passive"))
      (node (ref "U1") (pin "5") (pinfunction "VCC_5") (pintype "passive"))
    )
    (net (code "58") (name "unconnected-(J3-SBU1-PadA8)") (class "Default")
      (node (ref "J3") (pin "A8") (pinfunction "SBU1_A8") (pintype "passive"))
    )
    (net (code "59") (name "unconnected-(J3-SBU2-PadB8)") (class "Default")
      (node (ref "J3") (pin "B8") (pinfunction "SBU2_B8") (pintype "passive"))
    )
    (net (code "60") (name "unconnected-(J3-SSRXn1-PadB10)") (class "Default")
      (node (ref "J3") (pin "B10") (pinfunction "SSRXn1_B10") (pintype "passive"))
    )
    (net (code "61") (name "unconnected-(J3-SSRXn2-PadA10)") (class "Default")
      (node (ref "J3") (pin "A10") (pinfunction "SSRXn2_A10") (pintype "passive"))
    )
    (net (code "62") (name "unconnected-(J3-SSRXp1-PadB11)") (class "Default")
      (node (ref "J3") (pin "B11") (pinfunction "SSRXp1_B11") (pintype "passive"))
    )
    (net (code "63") (name "unconnected-(J3-SSRXp2-PadA11)") (class "Default")
      (node (ref "J3") (pin "A11") (pinfunction "SSRXp2_A11") (pintype "passive"))
    )
    (net (code "64") (name "unconnected-(J3-SSTXn1-PadA3)") (class "Default")
      (node (ref "J3") (pin "A3") (pinfunction "SSTXn1_A3") (pintype "passive"))
    )
    (net (code "65") (name "unconnected-(J3-SSTXn2-PadB3)") (class "Default")
      (node (ref "J3") (pin "B3") (pinfunction "SSTXn2_B3") (pintype "passive"))
    )
    (net (code "66") (name "unconnected-(J3-SSTXp1-PadA2)") (class "Default")
      (node (ref "J3") (pin "A2") (pinfunction "SSTXp1_A2") (pintype "passive"))
    )
    (net (code "67") (name "unconnected-(J3-SSTXp2-PadB2)") (class "Default")
      (node (ref "J3") (pin "B2") (pinfunction "SSTXp2_B2") (pintype "passive"))
    )
    (net (code "68") (name "unconnected-(J4-SHIELD1-Pad5)") (class "Default")
      (node (ref "J4") (pin "5") (pinfunction "SHIELD1_5") (pintype "passive"))
    )
    (net (code "69") (name "unconnected-(J4-SHIELD2-Pad6)") (class "Default")
      (node (ref "J4") (pin "6") (pinfunction "SHIELD2_6") (pintype "passive"))
    )
    (net (code "70") (name "unconnected-(Q1-D2-Pad5)") (class "Default")
      (node (ref "Q1") (pin "5") (pinfunction "D2_5") (pintype "passive"))
    )
    (net (code "71") (name "unconnected-(Q4-D1-Pad2)") (class "Default")
      (node (ref "Q4") (pin "2") (pinfunction "D1_2") (pintype "passive"))
    )
    (net (code "72") (name "unconnected-(Q5-D1-Pad2)") (class "Default")
      (node (ref "Q5") (pin "2") (pinfunction "D1_2") (pintype "passive"))
    )
    (net (code "73") (name "unconnected-(Q6-D1-Pad2)") (class "Default")
      (node (ref "Q6") (pin "2") (pinfunction "D1_2") (pintype "passive"))
    )
    (net (code "74") (name "unconnected-(Q7-D1-Pad2)") (class "Default")
      (node (ref "Q7") (pin "2") (pinfunction "D1_2") (pintype "passive"))
    )
    (net (code "75") (name "unconnected-(U1-TD-Pad4)") (class "Default")
      (node (ref "U1") (pin "4") (pinfunction "TD_4") (pintype "passive"))
    )
    (net (code "76") (name "unconnected-(U3-PA3-Pad4)") (class "Default")
      (node (ref "U3") (pin "4") (pinfunction "PA3_4") (pintype "passive"))
    )
    (net (code "77") (name "unconnected-(U3-PA7-Pad7)") (class "Default")
      (node (ref "U3") (pin "7") (pinfunction "PA7_7") (pintype "passive"))
    )
    (net (code "78") (name "unconnected-(U3-PB2-Pad6)") (class "Default")
      (node (ref "U3") (pin "6") (pinfunction "PB2_6") (pintype "passive"))
    )
  )
)
